# Drobit_ExtensionPanel.net
KiCad netlist of a schematic drawn in EAGLE
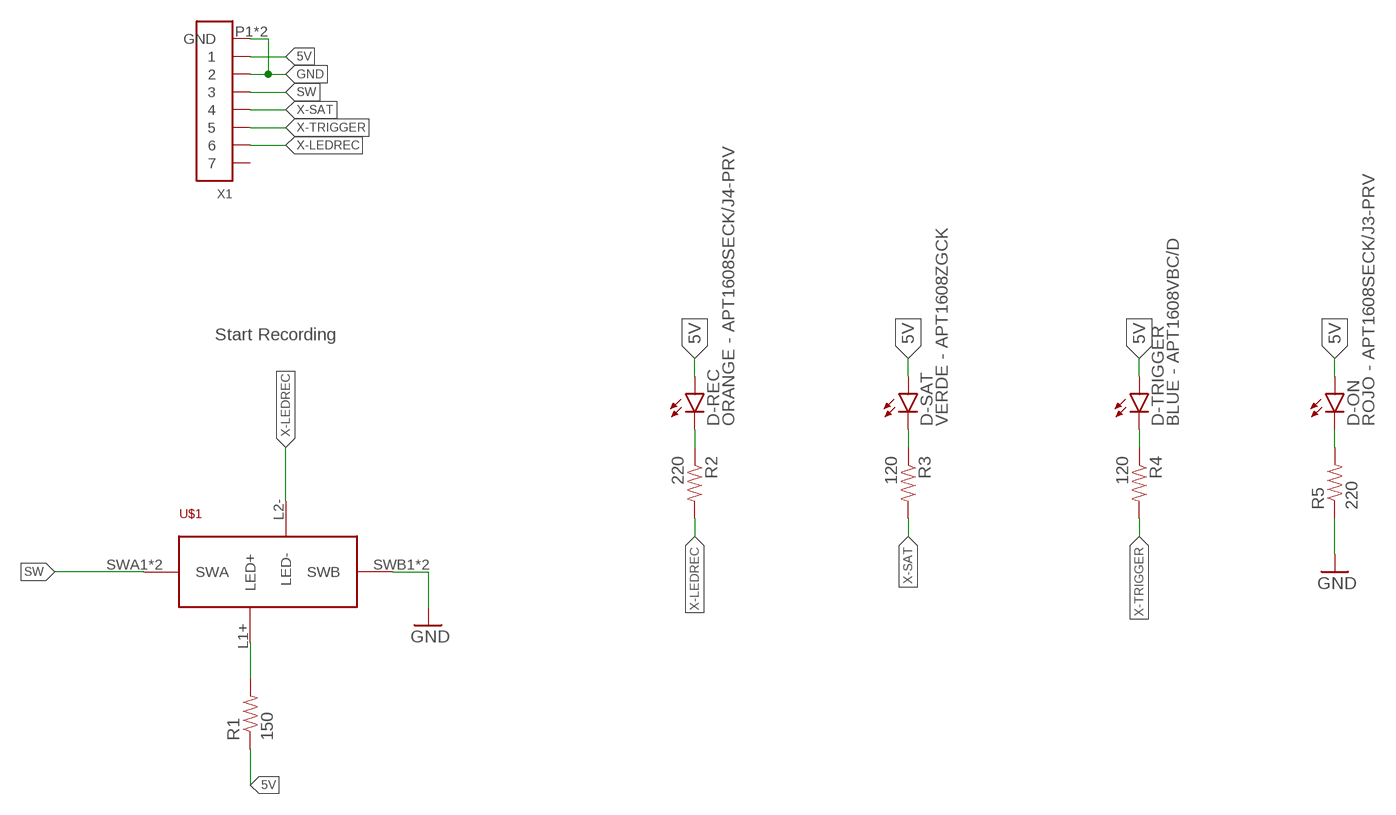
[diagram p0: schematic, sheet 1]

(export (version "E")
  (design (tool "Eeschema 10.0.6"))
  (components
    (comp (ref "D-ON")
      (value "ROJO - APT1608SECK/J3-PRV")
      (footprint "eagle-import:LED3MM")
      (fields (field (name "PARTNO") "604-APT1608SECKJ3PRV"))
      (libsource (lib "eagle-import") (part "LED3MM"))
    )
    (comp (ref "D-REC")
      (value "ORANGE - APT1608SECK/J4-PRV")
      (footprint "eagle-import:LED3MM")
      (fields (field (name "PARTNO") "604-APT1608SECKJ4PRV"))
      (libsource (lib "eagle-import") (part "LED3MM"))
    )
    (comp (ref "D-SAT")
      (value "VERDE - APT1608ZGCK")
      (footprint "eagle-import:LED3MM")
      (fields (field (name "PARTNO") "604-APT1608ZGCK"))
      (libsource (lib "eagle-import") (part "LED3MM"))
    )
    (comp (ref "D-TRIGGER")
      (value "BLUE - APT1608VBC/D")
      (footprint "eagle-import:LED3MM")
      (fields (field (name "PARTNO") "604-APT1608VBC/D"))
      (libsource (lib "eagle-import") (part "LED3MM"))
    )
    (comp (ref "R1")
      (value "150")
      (footprint "eagle-import:1206")
      (libsource (lib "eagle-import") (part "RESISTOR1206"))
    )
    (comp (ref "R2")
      (value "220")
      (footprint "eagle-import:1206")
      (fields (field (name "PARTNO") "667-ERJ-3GEYJ181V"))
      (libsource (lib "eagle-import") (part "RESISTOR1206"))
    )
    (comp (ref "R3")
      (value "120")
      (footprint "eagle-import:1206")
      (fields (field (name "PARTNO") "667-ERJ-3EKF1050V"))
      (libsource (lib "eagle-import") (part "RESISTOR1206"))
    )
    (comp (ref "R4")
      (value "120")
      (footprint "eagle-import:1206")
      (fields (field (name "PARTNO") "667-ERJ-3EKF1050V"))
      (libsource (lib "eagle-import") (part "RESISTOR1206"))
    )
    (comp (ref "R5")
      (value "220")
      (footprint "eagle-import:1206")
      (fields (field (name "PARTNO") "667-ERJ-3EKF82R0V"))
      (libsource (lib "eagle-import") (part "RESISTOR1206"))
    )
    (comp (ref "U$1")
      (value "PUSH-LED")
      (footprint "eagle-import:ITS13FV1ST")
      (libsource (lib "eagle-import") (part "PUSH-LED"))
    )
    (comp (ref "X1")
      (value "CONN_7-1")
      (footprint "eagle-import:JST-GH-7")
      (libsource (lib "eagle-import") (part "CONN_7-1"))
    )
  )
  (nets
    (net (code "1") (name "5V") (class "Default")
      (node (ref "D-ON") (pin "A") (pinfunction "A_A") (pintype "passive"))
      (node (ref "D-REC") (pin "A") (pinfunction "A_A") (pintype "passive"))
      (node (ref "D-SAT") (pin "A") (pinfunction "A_A") (pintype "passive"))
      (node (ref "D-TRIGGER") (pin "A") (pinfunction "A_A") (pintype "passive"))
      (node (ref "R1") (pin "1") (pinfunction "1_1") (pintype "passive"))
      (node (ref "X1") (pin "1") (pinfunction "1_1") (pintype "bidirectional"))
    )
    (net (code "2") (name "GND") (class "Default")
      (node (ref "R5") (pin "1") (pinfunction "1_1") (pintype "passive"))
      (node (ref "U$1") (pin "SWB1") (pinfunction "SWB_SWB1") (pintype "bidirectional"))
      (node (ref "U$1") (pin "SWB2") (pinfunction "SWB_SWB2") (pintype "bidirectional"))
      (node (ref "X1") (pin "2") (pinfunction "2_2") (pintype "bidirectional"))
      (node (ref "X1") (pin "P1") (pinfunction "GND_P1") (pintype "bidirectional"))
      (node (ref "X1") (pin "P2") (pinfunction "GND_P2") (pintype "bidirectional"))
    )
    (net (code "3") (name "Net-(D-ON-C)") (class "Default")
      (node (ref "D-ON") (pin "K") (pinfunction "C_K") (pintype "passive"))
      (node (ref "R5") (pin "2") (pinfunction "2_2") (pintype "passive"))
    )
    (net (code "4") (name "Net-(D-REC-C)") (class "Default")
      (node (ref "D-REC") (pin "K") (pinfunction "C_K") (pintype "passive"))
      (node (ref "R2") (pin "1") (pinfunction "1_1") (pintype "passive"))
    )
    (net (code "5") (name "Net-(D-SAT-C)") (class "Default")
      (node (ref "D-SAT") (pin "K") (pinfunction "C_K") (pintype "passive"))
      (node (ref "R3") (pin "1") (pinfunction "1_1") (pintype "passive"))
    )
    (net (code "6") (name "Net-(D-TRIGGER-C)") (class "Default")
      (node (ref "D-TRIGGER") (pin "K") (pinfunction "C_K") (pintype "passive"))
      (node (ref "R4") (pin "1") (pinfunction "1_1") (pintype "passive"))
    )
    (net (code "7") (name "Net-(U$1-LED+)") (class "Default")
      (node (ref "R1") (pin "2") (pinfunction "2_2") (pintype "passive"))
      (node (ref "U$1") (pin "L1+") (pinfunction "LED+_L1+") (pintype "bidirectional"))
    )
    (net (code "8") (name "SW") (class "Default")
      (node (ref "U$1") (pin "SWA1") (pinfunction "SWA_SWA1") (pintype "bidirectional"))
      (node (ref "U$1") (pin "SWA2") (pinfunction "SWA_SWA2") (pintype "bidirectional"))
      (node (ref "X1") (pin "3") (pinfunction "3_3") (pintype "bidirectional"))
    )
    (net (code "9") (name "X-LEDREC") (class "Default")
      (node (ref "R2") (pin "2") (pinfunction "2_2") (pintype "passive"))
      (node (ref "U$1") (pin "L2-") (pinfunction "LED-_L2-") (pintype "bidirectional"))
      (node (ref "X1") (pin "6") (pinfunction "6_6") (pintype "bidirectional"))
    )
    (net (code "10") (name "X-SAT") (class "Default")
      (node (ref "R3") (pin "2") (pinfunction "2_2") (pintype "passive"))
      (node (ref "X1") (pin "4") (pinfunction "4_4") (pintype "bidirectional"))
    )
    (net (code "11") (name "X-TRIGGER") (class "Default")
      (node (ref "R4") (pin "2") (pinfunction "2_2") (pintype "passive"))
      (node (ref "X1") (pin "5") (pinfunction "5_5") (pintype "bidirectional"))
    )
    (net (code "12") (name "unconnected-(X1-Pad7)") (class "Default")
      (node (ref "X1") (pin "7") (pinfunction "7_7") (pintype "bidirectional"))
    )
  )
)
